# Logic-Analyzer-01.net
KiCad netlist of a schematic drawn in Altium Designer
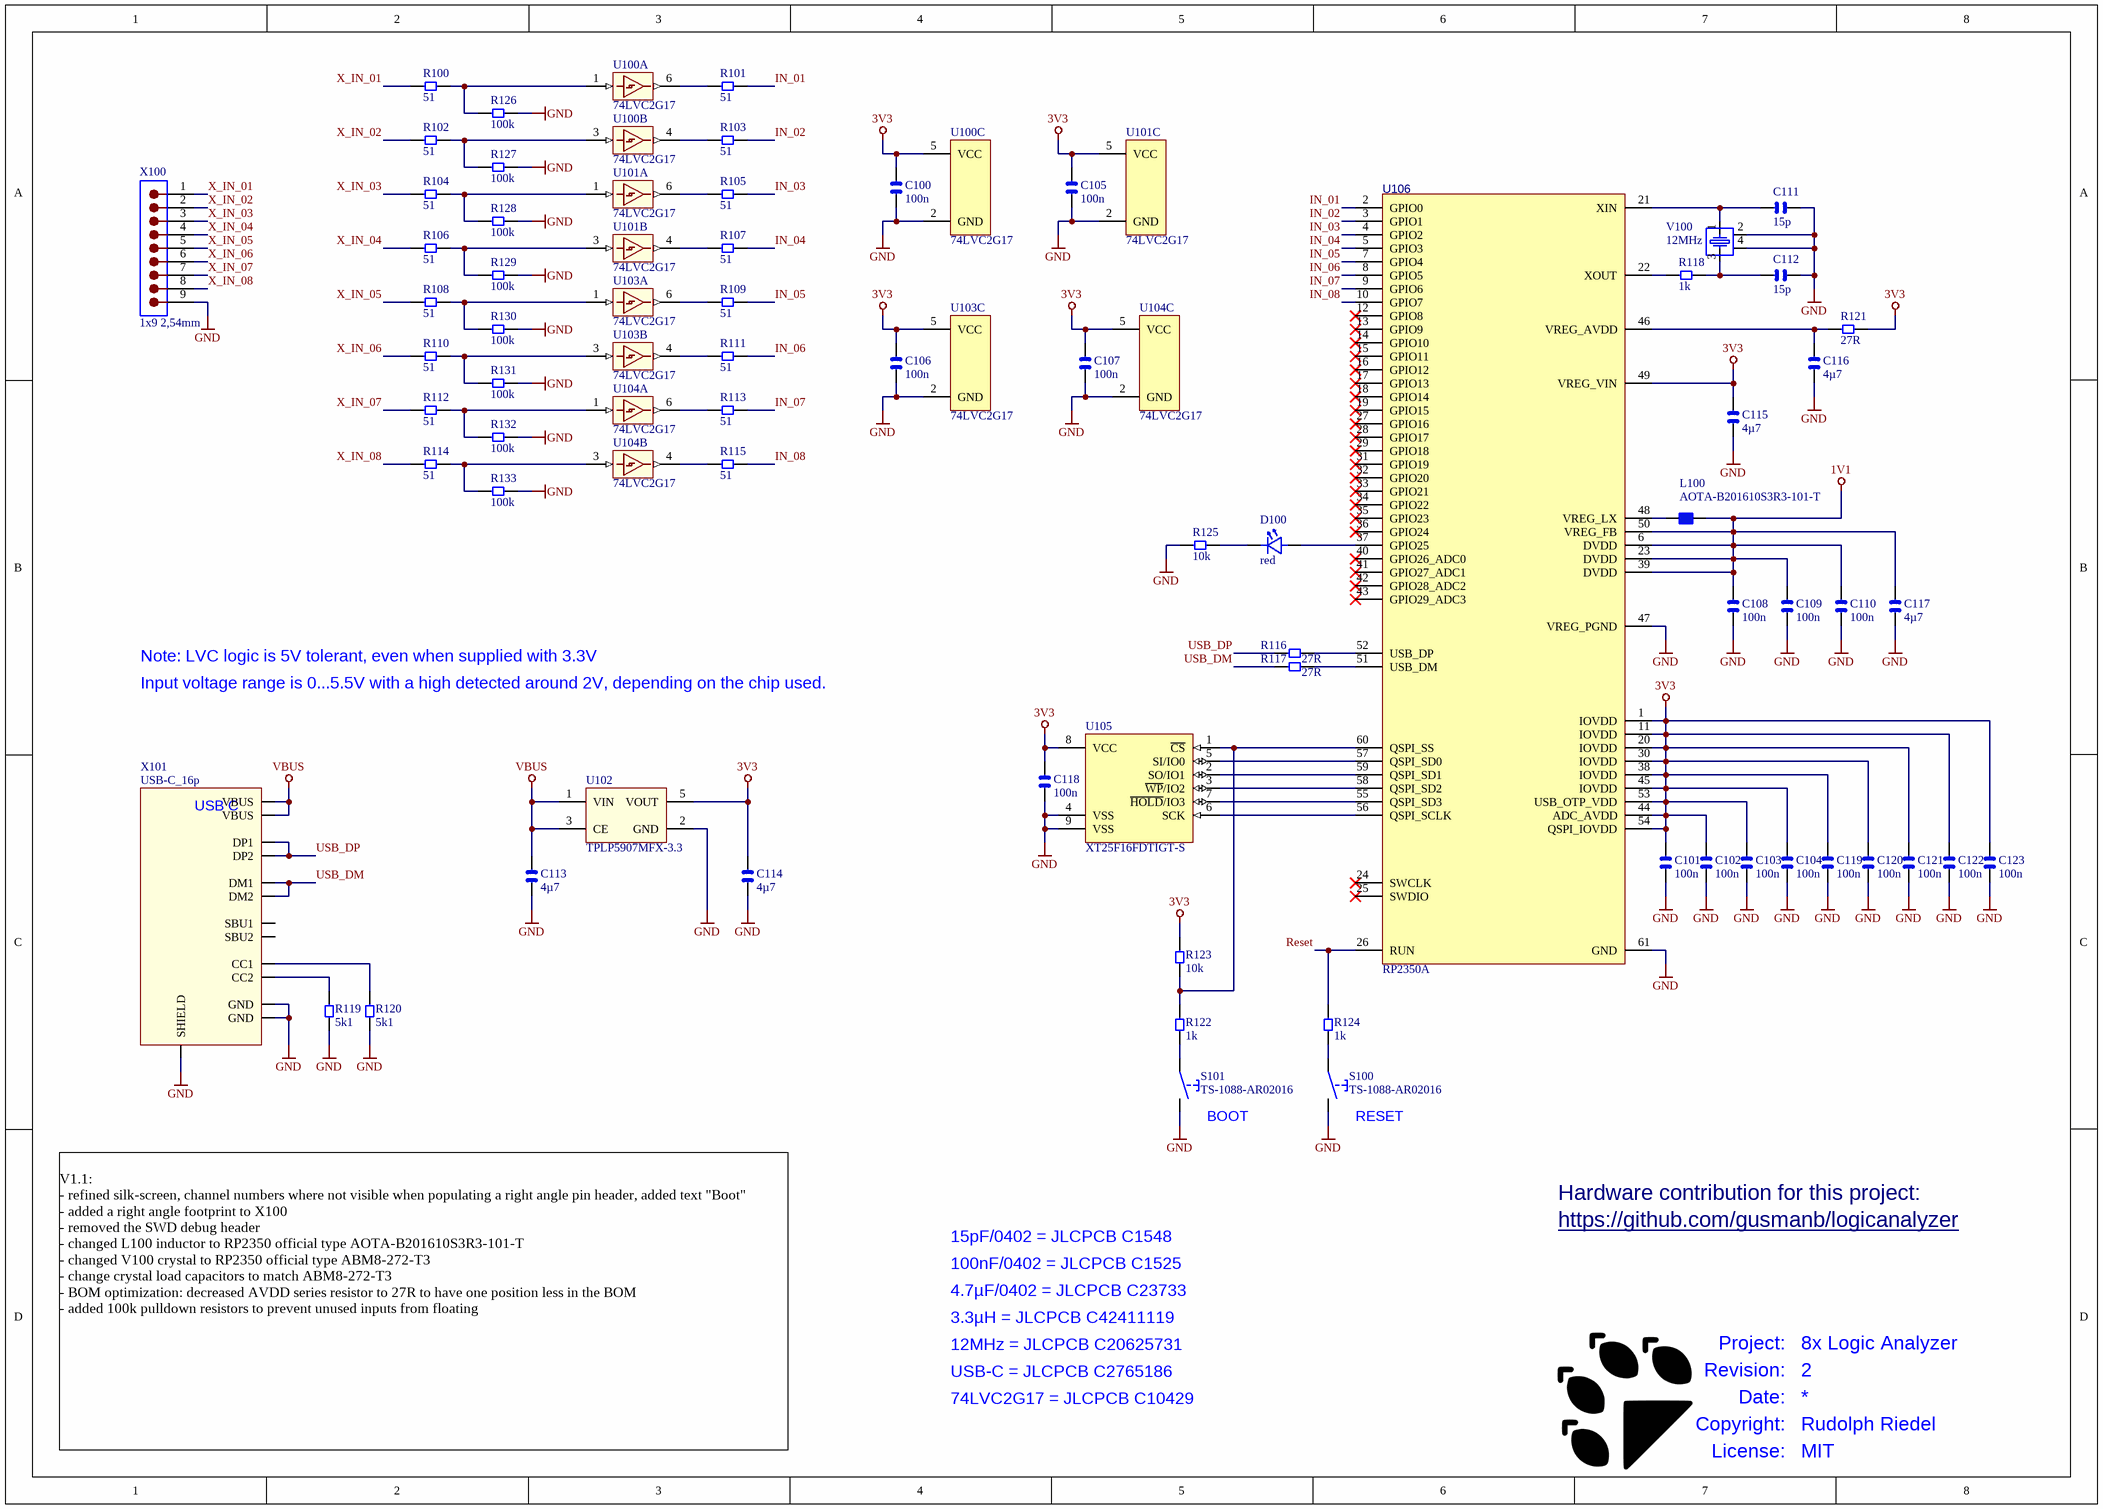
[diagram p0: Logic-Analyzer-01.SchDoc]

(export (version "E")
  (design (tool "Eeschema 10.0.6"))
  (components
    (comp (ref "C100")
      (value "100n")
      (footprint "CAPC1005X06N")
      (description "0402 Chip Capacitor")
      (fields (field (name "PART NUMBER") "CAPC_0402") (field (name "EDITOR") "rriedel"))
      (libsource (lib "HW-Labor_GF") (part "CAP_2_V2"))
    )
    (comp (ref "C101")
      (value "100n")
      (footprint "CAPC1005X06N")
      (description "0402 Chip Capacitor")
      (fields (field (name "PART NUMBER") "CAPC_0402") (field (name "EDITOR") "rriedel"))
      (libsource (lib "HW-Labor_GF") (part "CAP_2_V2"))
    )
    (comp (ref "C102")
      (value "100n")
      (footprint "CAPC1005X06N")
      (description "0402 Chip Capacitor")
      (fields (field (name "PART NUMBER") "CAPC_0402") (field (name "EDITOR") "rriedel"))
      (libsource (lib "HW-Labor_GF") (part "CAP_2_V2"))
    )
    (comp (ref "C103")
      (value "100n")
      (footprint "CAPC1005X06N")
      (description "0402 Chip Capacitor")
      (fields (field (name "PART NUMBER") "CAPC_0402") (field (name "EDITOR") "rriedel"))
      (libsource (lib "HW-Labor_GF") (part "CAP_2_V2"))
    )
    (comp (ref "C104")
      (value "100n")
      (footprint "CAPC1005X06N")
      (description "0402 Chip Capacitor")
      (fields (field (name "PART NUMBER") "CAPC_0402") (field (name "EDITOR") "rriedel"))
      (libsource (lib "HW-Labor_GF") (part "CAP_2_V2"))
    )
    (comp (ref "C105")
      (value "100n")
      (footprint "CAPC1005X06N")
      (description "0402 Chip Capacitor")
      (fields (field (name "PART NUMBER") "CAPC_0402") (field (name "EDITOR") "rriedel"))
      (libsource (lib "HW-Labor_GF") (part "CAP_2_V2"))
    )
    (comp (ref "C106")
      (value "100n")
      (footprint "CAPC1005X06N")
      (description "0402 Chip Capacitor")
      (fields (field (name "PART NUMBER") "CAPC_0402") (field (name "EDITOR") "rriedel"))
      (libsource (lib "HW-Labor_GF") (part "CAP_2_V2"))
    )
    (comp (ref "C107")
      (value "100n")
      (footprint "CAPC1005X06N")
      (description "0402 Chip Capacitor")
      (fields (field (name "PART NUMBER") "CAPC_0402") (field (name "EDITOR") "rriedel"))
      (libsource (lib "HW-Labor_GF") (part "CAP_2_V2"))
    )
    (comp (ref "C108")
      (value "100n")
      (footprint "CAPC1005X06N")
      (description "0402 Chip Capacitor")
      (fields (field (name "PART NUMBER") "CAPC_0402") (field (name "EDITOR") "rriedel"))
      (libsource (lib "HW-Labor_GF") (part "CAP_2_V2"))
    )
    (comp (ref "C109")
      (value "100n")
      (footprint "CAPC1005X06N")
      (description "0402 Chip Capacitor")
      (fields (field (name "PART NUMBER") "CAPC_0402") (field (name "EDITOR") "rriedel"))
      (libsource (lib "HW-Labor_GF") (part "CAP_2_V2"))
    )
    (comp (ref "C110")
      (value "100n")
      (footprint "CAPC1005X06N")
      (description "0402 Chip Capacitor")
      (fields (field (name "PART NUMBER") "CAPC_0402") (field (name "EDITOR") "rriedel"))
      (libsource (lib "HW-Labor_GF") (part "CAP_2_V2"))
    )
    (comp (ref "C111")
      (value "15p")
      (footprint "CAPC1005X06N")
      (description "0402 Chip Capacitor")
      (fields (field (name "PART NUMBER") "CAPC_0402") (field (name "EDITOR") "rriedel"))
      (libsource (lib "HW-Labor_GF") (part "CAP_2_V2"))
    )
    (comp (ref "C112")
      (value "15p")
      (footprint "CAPC1005X06N")
      (description "0402 Chip Capacitor")
      (fields (field (name "PART NUMBER") "CAPC_0402") (field (name "EDITOR") "rriedel"))
      (libsource (lib "HW-Labor_GF") (part "CAP_2_V2"))
    )
    (comp (ref "C113")
      (value "4µ7")
      (footprint "CAPC1005X06N")
      (description "0402 Chip Capacitor")
      (fields (field (name "PART NUMBER") "CAPC_0402") (field (name "EDITOR") "rriedel"))
      (libsource (lib "HW-Labor_GF") (part "CAP_2_V2"))
    )
    (comp (ref "C114")
      (value "4µ7")
      (footprint "CAPC1005X06N")
      (description "0402 Chip Capacitor")
      (fields (field (name "PART NUMBER") "CAPC_0402") (field (name "EDITOR") "rriedel"))
      (libsource (lib "HW-Labor_GF") (part "CAP_2_V2"))
    )
    (comp (ref "C115")
      (value "4µ7")
      (footprint "CAPC1005X06N")
      (description "0402 Chip Capacitor")
      (fields (field (name "PART NUMBER") "CAPC_0402") (field (name "EDITOR") "rriedel"))
      (libsource (lib "HW-Labor_GF") (part "CAP_2_V2"))
    )
    (comp (ref "C116")
      (value "4µ7")
      (footprint "CAPC1005X06N")
      (description "0402 Chip Capacitor")
      (fields (field (name "PART NUMBER") "CAPC_0402") (field (name "EDITOR") "rriedel"))
      (libsource (lib "HW-Labor_GF") (part "CAP_2_V2"))
    )
    (comp (ref "C117")
      (value "4µ7")
      (footprint "CAPC1005X06N")
      (description "0402 Chip Capacitor")
      (fields (field (name "PART NUMBER") "CAPC_0402") (field (name "EDITOR") "rriedel"))
      (libsource (lib "HW-Labor_GF") (part "CAP_2_V2"))
    )
    (comp (ref "C118")
      (value "100n")
      (footprint "CAPC1005X06N")
      (description "0402 Chip Capacitor")
      (fields (field (name "PART NUMBER") "CAPC_0402") (field (name "EDITOR") "rriedel"))
      (libsource (lib "HW-Labor_GF") (part "CAP_2_V2"))
    )
    (comp (ref "C119")
      (value "100n")
      (footprint "CAPC1005X06N")
      (description "0402 Chip Capacitor")
      (fields (field (name "PART NUMBER") "CAPC_0402") (field (name "EDITOR") "rriedel"))
      (libsource (lib "HW-Labor_GF") (part "CAP_2_V2"))
    )
    (comp (ref "C120")
      (value "100n")
      (footprint "CAPC1005X06N")
      (description "0402 Chip Capacitor")
      (fields (field (name "PART NUMBER") "CAPC_0402") (field (name "EDITOR") "rriedel"))
      (libsource (lib "HW-Labor_GF") (part "CAP_2_V2"))
    )
    (comp (ref "C121")
      (value "100n")
      (footprint "CAPC1005X06N")
      (description "0402 Chip Capacitor")
      (fields (field (name "PART NUMBER") "CAPC_0402") (field (name "EDITOR") "rriedel"))
      (libsource (lib "HW-Labor_GF") (part "CAP_2_V2"))
    )
    (comp (ref "C122")
      (value "100n")
      (footprint "CAPC1005X06N")
      (description "0402 Chip Capacitor")
      (fields (field (name "PART NUMBER") "CAPC_0402") (field (name "EDITOR") "rriedel"))
      (libsource (lib "HW-Labor_GF") (part "CAP_2_V2"))
    )
    (comp (ref "C123")
      (value "100n")
      (footprint "CAPC1005X06N")
      (description "0402 Chip Capacitor")
      (fields (field (name "PART NUMBER") "CAPC_0402") (field (name "EDITOR") "rriedel"))
      (libsource (lib "HW-Labor_GF") (part "CAP_2_V2"))
    )
    (comp (ref "D100")
      (value "red")
      (footprint "DIOC1608X06N_LED")
      (description "LED, 0603")
      (fields (field (name "PART NUMBER") "LED_0603") (field (name "EDITOR") "rriedel"))
      (libsource (lib "HW-Labor_GF") (part "LED_generic"))
    )
    (comp (ref "L100")
      (value "AOTA-B201610S3R3-101-T")
      (footprint "PowerInductor_2.0x1.6")
      (description "3.3µH, 2.8A, 2.0mm x 1.6mm x 1.0mm")
      (fields
        (field (name "MANUFACTURER") "Abracom")
        (field (name "DISTRIBUTOR_1_PART_NUMBER") "C42411119")
        (field (name "EDITOR") "rriedel")
      )
      (libsource (lib "HW-Labor_GF") (part "IND_2_V1"))
    )
    (comp (ref "R100")
      (value "51")
      (footprint "RESC1608X06L")
      (description "0603 Chip Resistor")
      (fields (field (name "PART NUMBER") "RESC_0603") (field (name "EDITOR") "rriedel"))
      (libsource (lib "HW-Labor_GF") (part "RES_2_V2"))
    )
    (comp (ref "R101")
      (value "51")
      (footprint "RESC1608X06L")
      (description "0603 Chip Resistor")
      (fields (field (name "PART NUMBER") "RESC_0603") (field (name "EDITOR") "rriedel"))
      (libsource (lib "HW-Labor_GF") (part "RES_2_V2"))
    )
    (comp (ref "R102")
      (value "51")
      (footprint "RESC1608X06L")
      (description "0603 Chip Resistor")
      (fields (field (name "PART NUMBER") "RESC_0603") (field (name "EDITOR") "rriedel"))
      (libsource (lib "HW-Labor_GF") (part "RES_2_V2"))
    )
    (comp (ref "R103")
      (value "51")
      (footprint "RESC1608X06L")
      (description "0603 Chip Resistor")
      (fields (field (name "PART NUMBER") "RESC_0603") (field (name "EDITOR") "rriedel"))
      (libsource (lib "HW-Labor_GF") (part "RES_2_V2"))
    )
    (comp (ref "R104")
      (value "51")
      (footprint "RESC1608X06L")
      (description "0603 Chip Resistor")
      (fields (field (name "PART NUMBER") "RESC_0603") (field (name "EDITOR") "rriedel"))
      (libsource (lib "HW-Labor_GF") (part "RES_2_V2"))
    )
    (comp (ref "R105")
      (value "51")
      (footprint "RESC1608X06L")
      (description "0603 Chip Resistor")
      (fields (field (name "PART NUMBER") "RESC_0603") (field (name "EDITOR") "rriedel"))
      (libsource (lib "HW-Labor_GF") (part "RES_2_V2"))
    )
    (comp (ref "R106")
      (value "51")
      (footprint "RESC1608X06L")
      (description "0603 Chip Resistor")
      (fields (field (name "PART NUMBER") "RESC_0603") (field (name "EDITOR") "rriedel"))
      (libsource (lib "HW-Labor_GF") (part "RES_2_V2"))
    )
    (comp (ref "R107")
      (value "51")
      (footprint "RESC1608X06L")
      (description "0603 Chip Resistor")
      (fields (field (name "PART NUMBER") "RESC_0603") (field (name "EDITOR") "rriedel"))
      (libsource (lib "HW-Labor_GF") (part "RES_2_V2"))
    )
    (comp (ref "R108")
      (value "51")
      (footprint "RESC1608X06L")
      (description "0603 Chip Resistor")
      (fields (field (name "PART NUMBER") "RESC_0603") (field (name "EDITOR") "rriedel"))
      (libsource (lib "HW-Labor_GF") (part "RES_2_V2"))
    )
    (comp (ref "R109")
      (value "51")
      (footprint "RESC1608X06L")
      (description "0603 Chip Resistor")
      (fields (field (name "PART NUMBER") "RESC_0603") (field (name "EDITOR") "rriedel"))
      (libsource (lib "HW-Labor_GF") (part "RES_2_V2"))
    )
    (comp (ref "R110")
      (value "51")
      (footprint "RESC1608X06L")
      (description "0603 Chip Resistor")
      (fields (field (name "PART NUMBER") "RESC_0603") (field (name "EDITOR") "rriedel"))
      (libsource (lib "HW-Labor_GF") (part "RES_2_V2"))
    )
    (comp (ref "R111")
      (value "51")
      (footprint "RESC1608X06L")
      (description "0603 Chip Resistor")
      (fields (field (name "PART NUMBER") "RESC_0603") (field (name "EDITOR") "rriedel"))
      (libsource (lib "HW-Labor_GF") (part "RES_2_V2"))
    )
    (comp (ref "R112")
      (value "51")
      (footprint "RESC1608X06L")
      (description "0603 Chip Resistor")
      (fields (field (name "PART NUMBER") "RESC_0603") (field (name "EDITOR") "rriedel"))
      (libsource (lib "HW-Labor_GF") (part "RES_2_V2"))
    )
    (comp (ref "R113")
      (value "51")
      (footprint "RESC1608X06L")
      (description "0603 Chip Resistor")
      (fields (field (name "PART NUMBER") "RESC_0603") (field (name "EDITOR") "rriedel"))
      (libsource (lib "HW-Labor_GF") (part "RES_2_V2"))
    )
    (comp (ref "R114")
      (value "51")
      (footprint "RESC1608X06L")
      (description "0603 Chip Resistor")
      (fields (field (name "PART NUMBER") "RESC_0603") (field (name "EDITOR") "rriedel"))
      (libsource (lib "HW-Labor_GF") (part "RES_2_V2"))
    )
    (comp (ref "R115")
      (value "51")
      (footprint "RESC1608X06L")
      (description "0603 Chip Resistor")
      (fields (field (name "PART NUMBER") "RESC_0603") (field (name "EDITOR") "rriedel"))
      (libsource (lib "HW-Labor_GF") (part "RES_2_V2"))
    )
    (comp (ref "R116")
      (value "27R")
      (footprint "RESC1608X06L")
      (description "0603 Chip Resistor")
      (fields (field (name "PART NUMBER") "RESC_0603") (field (name "EDITOR") "rriedel"))
      (libsource (lib "HW-Labor_GF") (part "RES_2_V2"))
    )
    (comp (ref "R117")
      (value "27R")
      (footprint "RESC1608X06L")
      (description "0603 Chip Resistor")
      (fields (field (name "PART NUMBER") "RESC_0603") (field (name "EDITOR") "rriedel"))
      (libsource (lib "HW-Labor_GF") (part "RES_2_V2"))
    )
    (comp (ref "R118")
      (value "1k")
      (footprint "RESC1608X06L")
      (description "0603 Chip Resistor")
      (fields (field (name "PART NUMBER") "RESC_0603") (field (name "EDITOR") "rriedel"))
      (libsource (lib "HW-Labor_GF") (part "RES_2_V2"))
    )
    (comp (ref "R119")
      (value "5k1")
      (footprint "RESC1608X06L")
      (description "0603 Chip Resistor")
      (fields (field (name "PART NUMBER") "RESC_0603") (field (name "EDITOR") "rriedel"))
      (libsource (lib "HW-Labor_GF") (part "RES_2_V2"))
    )
    (comp (ref "R120")
      (value "5k1")
      (footprint "RESC1608X06L")
      (description "0603 Chip Resistor")
      (fields (field (name "PART NUMBER") "RESC_0603") (field (name "EDITOR") "rriedel"))
      (libsource (lib "HW-Labor_GF") (part "RES_2_V2"))
    )
    (comp (ref "R121")
      (value "27R")
      (footprint "RESC1608X06L")
      (description "0603 Chip Resistor")
      (fields (field (name "PART NUMBER") "RESC_0603") (field (name "EDITOR") "rriedel"))
      (libsource (lib "HW-Labor_GF") (part "RES_2_V2"))
    )
    (comp (ref "R122")
      (value "1k")
      (footprint "RESC1608X06L")
      (description "0603 Chip Resistor")
      (fields (field (name "PART NUMBER") "RESC_0603") (field (name "EDITOR") "rriedel"))
      (libsource (lib "HW-Labor_GF") (part "RES_2_V2"))
    )
    (comp (ref "R123")
      (value "10k")
      (footprint "RESC1608X06L")
      (description "0603 Chip Resistor")
      (fields (field (name "PART NUMBER") "RESC_0603") (field (name "EDITOR") "rriedel"))
      (libsource (lib "HW-Labor_GF") (part "RES_2_V2"))
    )
    (comp (ref "R124")
      (value "1k")
      (footprint "RESC1608X06L")
      (description "0603 Chip Resistor")
      (fields (field (name "PART NUMBER") "RESC_0603") (field (name "EDITOR") "rriedel"))
      (libsource (lib "HW-Labor_GF") (part "RES_2_V2"))
    )
    (comp (ref "R125")
      (value "10k")
      (footprint "RESC1608X06L")
      (description "0603 Chip Resistor")
      (fields (field (name "PART NUMBER") "RESC_0603") (field (name "EDITOR") "rriedel"))
      (libsource (lib "HW-Labor_GF") (part "RES_2_V2"))
    )
    (comp (ref "R126")
      (value "100k")
      (footprint "RESC1005X06N")
      (description "0402 Chip Resistor")
      (fields (field (name "PART NUMBER") "RESC_0402") (field (name "EDITOR") "rriedel"))
      (libsource (lib "HW-Labor_GF") (part "RES_2_V2"))
    )
    (comp (ref "R127")
      (value "100k")
      (footprint "RESC1005X06N")
      (description "0402 Chip Resistor")
      (fields (field (name "PART NUMBER") "RESC_0402") (field (name "EDITOR") "rriedel"))
      (libsource (lib "HW-Labor_GF") (part "RES_2_V2"))
    )
    (comp (ref "R128")
      (value "100k")
      (footprint "RESC1005X06N")
      (description "0402 Chip Resistor")
      (fields (field (name "PART NUMBER") "RESC_0402") (field (name "EDITOR") "rriedel"))
      (libsource (lib "HW-Labor_GF") (part "RES_2_V2"))
    )
    (comp (ref "R129")
      (value "100k")
      (footprint "RESC1005X06N")
      (description "0402 Chip Resistor")
      (fields (field (name "PART NUMBER") "RESC_0402") (field (name "EDITOR") "rriedel"))
      (libsource (lib "HW-Labor_GF") (part "RES_2_V2"))
    )
    (comp (ref "R130")
      (value "100k")
      (footprint "RESC1005X06N")
      (description "0402 Chip Resistor")
      (fields (field (name "PART NUMBER") "RESC_0402") (field (name "EDITOR") "rriedel"))
      (libsource (lib "HW-Labor_GF") (part "RES_2_V2"))
    )
    (comp (ref "R131")
      (value "100k")
      (footprint "RESC1005X06N")
      (description "0402 Chip Resistor")
      (fields (field (name "PART NUMBER") "RESC_0402") (field (name "EDITOR") "rriedel"))
      (libsource (lib "HW-Labor_GF") (part "RES_2_V2"))
    )
    (comp (ref "R132")
      (value "100k")
      (footprint "RESC1005X06N")
      (description "0402 Chip Resistor")
      (fields (field (name "PART NUMBER") "RESC_0402") (field (name "EDITOR") "rriedel"))
      (libsource (lib "HW-Labor_GF") (part "RES_2_V2"))
    )
    (comp (ref "R133")
      (value "100k")
      (footprint "RESC1005X06N")
      (description "0402 Chip Resistor")
      (fields (field (name "PART NUMBER") "RESC_0402") (field (name "EDITOR") "rriedel"))
      (libsource (lib "HW-Labor_GF") (part "RES_2_V2"))
    )
    (comp (ref "S100")
      (value "TS-1088-AR02016")
      (footprint "TS-1088-AR02016")
      (description "Tact Switch, 4x3x2, 2pin, 12V/50mA")
      (fields
        (field (name "MANUFACTURER") "XunPu")
        (field (name "DISTRIBUTOR_1_PART_NUMBER") "C720477")
        (field (name "EDITOR") "rriedel")
      )
      (libsource (lib "HW-Labor_GF") (part "Tact_Switch"))
    )
    (comp (ref "S101")
      (value "TS-1088-AR02016")
      (footprint "TS-1088-AR02016")
      (description "Tact Switch, 4x3x2, 2pin, 12V/50mA")
      (fields
        (field (name "MANUFACTURER") "XunPu")
        (field (name "DISTRIBUTOR_1_PART_NUMBER") "C720477")
        (field (name "EDITOR") "rriedel")
      )
      (libsource (lib "HW-Labor_GF") (part "Tact_Switch"))
    )
    (comp (ref "U100")
      (value "74LVC2G17")
      (footprint "SOT95P280X110-6N")
      (description "Dual Schmitt-Trigger Buffer with 5.5V tolerant inputs")
      (fields
        (field (name "MANUFACTURER") "TI")
        (field (name "DISTRIBUTOR_1_PART_NUMBER") "296-SN74LVC2G17DBVRCT-ND‎")
        (field (name "EDITOR") "rriedel")
      )
      (libsource (lib "HW-Labor_GF") (part "74LVC2G17"))
    )
    (comp (ref "U101")
      (value "74LVC2G17")
      (footprint "SOT95P280X110-6N")
      (description "Dual Schmitt-Trigger Buffer with 5.5V tolerant inputs")
      (fields
        (field (name "MANUFACTURER") "TI")
        (field (name "DISTRIBUTOR_1_PART_NUMBER") "296-SN74LVC2G17DBVRCT-ND‎")
        (field (name "EDITOR") "rriedel")
      )
      (libsource (lib "HW-Labor_GF") (part "74LVC2G17"))
    )
    (comp (ref "U102")
      (value "TPLP5907MFX-3.3")
      (footprint "SOT95P280X110-5N")
      (description "100 mA LDO,  Vout= 3,3V, -40°C..125°C")
      (fields
        (field (name "PART NUMBER") "MIC5233-3.3")
        (field (name "MANUFACTURER") "Microchip")
        (field (name "EDITOR") "rriedel")
      )
      (libsource (lib "HW-Labor_GF") (part "LDO_SOT23-5"))
    )
    (comp (ref "U103")
      (value "74LVC2G17")
      (footprint "SOT95P280X110-6N")
      (description "Dual Schmitt-Trigger Buffer with 5.5V tolerant inputs")
      (fields
        (field (name "MANUFACTURER") "TI")
        (field (name "DISTRIBUTOR_1_PART_NUMBER") "296-SN74LVC2G17DBVRCT-ND‎")
        (field (name "EDITOR") "rriedel")
      )
      (libsource (lib "HW-Labor_GF") (part "74LVC2G17"))
    )
    (comp (ref "U104")
      (value "74LVC2G17")
      (footprint "SOT95P280X110-6N")
      (description "Dual Schmitt-Trigger Buffer with 5.5V tolerant inputs")
      (fields
        (field (name "MANUFACTURER") "TI")
        (field (name "DISTRIBUTOR_1_PART_NUMBER") "296-SN74LVC2G17DBVRCT-ND‎")
        (field (name "EDITOR") "rriedel")
      )
      (libsource (lib "HW-Labor_GF") (part "74LVC2G17"))
    )
    (comp (ref "U105")
      (value "XT25F16FDTIGT-S")
      (footprint "USONP50X200X300X8N")
      (description "SPI NOR FLASH, 16MBit")
      (fields
        (field (name "MANUFACTURER") "XTX")
        (field (name "DISTRIBUTOR_1_PART_NUMBER") "C29781641")
        (field (name "EDITOR") "rriedel")
      )
      (libsource (lib "HW-Labor_GF") (part "SPI_NOR_USON8"))
    )
    (comp (ref "U106")
      (value "RP2350A")
      (footprint "QFN40P700X700X085-60EP")
      (description "32-bit Microcontroller, 2x 150MHz Cortex M33")
      (fields (field (name "MANUFACTURER") "Raspberry") (field (name "EDITOR") "rriedel"))
      (libsource (lib "HW-Labor_GF") (part "RP2350A"))
    )
    (comp (ref "V100")
      (value "12MHz")
      (footprint "ABM8")
      (description "-40℃~+85℃, 12MHz, Cl=10pF, ±30ppm, SMD3225-4P")
      (fields
        (field (name "PART NUMBER") "ABM8-272-T3")
        (field (name "MANUFACTURER") "Abracom")
        (field (name "EDITOR") "rriedel")
      )
      (libsource (lib "HW-Labor_GF") (part "XTAL_SMD-4"))
    )
    (comp (ref "X100")
      (value "1x9 2,54mm")
      (footprint "PINH_1x09_2_54mm_RA")
      (description "Pin-Header 2,54 mm 9pins")
      (fields (field (name "PART NUMBER") "PINH_1x9_2_54") (field (name "EDITOR") "rriedel"))
      (libsource (lib "HW-Labor_GF") (part "CONM_1x9_V2"))
    )
    (comp (ref "X101")
      (value "USB-C_16p")
      (footprint "USBC_16P")
      (description "SMD USB-C 16p")
      (fields (field (name "DISTRIBUTOR_1_PART_NUMBER") "C2765186") (field (name "EDITOR") "rriedel"))
      (libsource (lib "HW-Labor_GF") (part "USB-C"))
    )
  )
  (nets
    (net (code "1") (name "/IN_01") (class "Default")
      (node (ref "R101") (pin "2") (pinfunction "2_2") (pintype "passive"))
      (node (ref "U106") (pin "2") (pinfunction "GPIO0_2") (pintype "passive"))
    )
    (net (code "2") (name "/IN_02") (class "Default")
      (node (ref "R103") (pin "2") (pinfunction "2_2") (pintype "passive"))
      (node (ref "U106") (pin "3") (pinfunction "GPIO1_3") (pintype "passive"))
    )
    (net (code "3") (name "/IN_03") (class "Default")
      (node (ref "R105") (pin "2") (pinfunction "2_2") (pintype "passive"))
      (node (ref "U106") (pin "4") (pinfunction "GPIO2_4") (pintype "passive"))
    )
    (net (code "4") (name "/IN_04") (class "Default")
      (node (ref "R107") (pin "2") (pinfunction "2_2") (pintype "passive"))
      (node (ref "U106") (pin "5") (pinfunction "GPIO3_5") (pintype "passive"))
    )
    (net (code "5") (name "/IN_05") (class "Default")
      (node (ref "R109") (pin "2") (pinfunction "2_2") (pintype "passive"))
      (node (ref "U106") (pin "7") (pinfunction "GPIO4_7") (pintype "passive"))
    )
    (net (code "6") (name "/IN_06") (class "Default")
      (node (ref "R111") (pin "2") (pinfunction "2_2") (pintype "passive"))
      (node (ref "U106") (pin "8") (pinfunction "GPIO5_8") (pintype "passive"))
    )
    (net (code "7") (name "/IN_07") (class "Default")
      (node (ref "R113") (pin "2") (pinfunction "2_2") (pintype "passive"))
      (node (ref "U106") (pin "9") (pinfunction "GPIO6_9") (pintype "passive"))
    )
    (net (code "8") (name "/IN_08") (class "Default")
      (node (ref "R115") (pin "2") (pinfunction "2_2") (pintype "passive"))
      (node (ref "U106") (pin "10") (pinfunction "GPIO7_10") (pintype "passive"))
    )
    (net (code "9") (name "/Reset") (class "Default")
      (node (ref "R124") (pin "2") (pinfunction "2_2") (pintype "passive"))
      (node (ref "U106") (pin "26") (pinfunction "RUN_26") (pintype "passive"))
    )
    (net (code "10") (name "/USB_DM") (class "Default")
      (node (ref "R117") (pin "1") (pinfunction "1_1") (pintype "passive"))
      (node (ref "X101") (pin "A7") (pinfunction "DM1_A7") (pintype "passive"))
      (node (ref "X101") (pin "B7") (pinfunction "DM2_B7") (pintype "passive"))
    )
    (net (code "11") (name "/USB_DP") (class "Default")
      (node (ref "R116") (pin "1") (pinfunction "1_1") (pintype "passive"))
      (node (ref "X101") (pin "A6") (pinfunction "DP1_A6") (pintype "passive"))
      (node (ref "X101") (pin "B6") (pinfunction "DP2_B6") (pintype "passive"))
    )
    (net (code "12") (name "/X_IN_01") (class "Default")
      (node (ref "R100") (pin "1") (pinfunction "1_1") (pintype "passive"))
      (node (ref "X100") (pin "1") (pinfunction "1_1") (pintype "passive"))
    )
    (net (code "13") (name "/X_IN_02") (class "Default")
      (node (ref "R102") (pin "1") (pinfunction "1_1") (pintype "passive"))
      (node (ref "X100") (pin "2") (pinfunction "2_2") (pintype "passive"))
    )
    (net (code "14") (name "/X_IN_03") (class "Default")
      (node (ref "R104") (pin "1") (pinfunction "1_1") (pintype "passive"))
      (node (ref "X100") (pin "3") (pinfunction "3_3") (pintype "passive"))
    )
    (net (code "15") (name "/X_IN_04") (class "Default")
      (node (ref "R106") (pin "1") (pinfunction "1_1") (pintype "passive"))
      (node (ref "X100") (pin "4") (pinfunction "4_4") (pintype "passive"))
    )
    (net (code "16") (name "/X_IN_05") (class "Default")
      (node (ref "R108") (pin "1") (pinfunction "1_1") (pintype "passive"))
      (node (ref "X100") (pin "5") (pinfunction "5_5") (pintype "passive"))
    )
    (net (code "17") (name "/X_IN_06") (class "Default")
      (node (ref "R110") (pin "1") (pinfunction "1_1") (pintype "passive"))
      (node (ref "X100") (pin "6") (pinfunction "6_6") (pintype "passive"))
    )
    (net (code "18") (name "/X_IN_07") (class "Default")
      (node (ref "R112") (pin "1") (pinfunction "1_1") (pintype "passive"))
      (node (ref "X100") (pin "7") (pinfunction "7_7") (pintype "passive"))
    )
    (net (code "19") (name "/X_IN_08") (class "Default")
      (node (ref "R114") (pin "1") (pinfunction "1_1") (pintype "passive"))
      (node (ref "X100") (pin "8") (pinfunction "8_8") (pintype "passive"))
    )
    (net (code "20") (name "1V1") (class "Default")
      (node (ref "C108") (pin "2") (pinfunction "2_2") (pintype "passive"))
      (node (ref "C109") (pin "2") (pinfunction "2_2") (pintype "passive"))
      (node (ref "C110") (pin "2") (pinfunction "2_2") (pintype "passive"))
      (node (ref "C117") (pin "2") (pinfunction "2_2") (pintype "passive"))
      (node (ref "L100") (pin "1") (pinfunction "1_1") (pintype "passive"))
      (node (ref "U106") (pin "23") (pinfunction "DVDD_23") (pintype "power_in"))
      (node (ref "U106") (pin "39") (pinfunction "DVDD_39") (pintype "power_in"))
      (node (ref "U106") (pin "50") (pinfunction "VREG_FB_50") (pintype "passive"))
      (node (ref "U106") (pin "6") (pinfunction "DVDD_6") (pintype "power_in"))
    )
    (net (code "21") (name "3V3") (class "Default")
      (node (ref "C100") (pin "2") (pinfunction "2_2") (pintype "passive"))
      (node (ref "C101") (pin "2") (pinfunction "2_2") (pintype "passive"))
      (node (ref "C102") (pin "2") (pinfunction "2_2") (pintype "passive"))
      (node (ref "C103") (pin "2") (pinfunction "2_2") (pintype "passive"))
      (node (ref "C104") (pin "2") (pinfunction "2_2") (pintype "passive"))
      (node (ref "C105") (pin "2") (pinfunction "2_2") (pintype "passive"))
      (node (ref "C106") (pin "2") (pinfunction "2_2") (pintype "passive"))
      (node (ref "C107") (pin "2") (pinfunction "2_2") (pintype "passive"))
      (node (ref "C114") (pin "2") (pinfunction "2_2") (pintype "passive"))
      (node (ref "C115") (pin "2") (pinfunction "2_2") (pintype "passive"))
      (node (ref "C118") (pin "2") (pinfunction "2_2") (pintype "passive"))
      (node (ref "C119") (pin "2") (pinfunction "2_2") (pintype "passive"))
      (node (ref "C120") (pin "2") (pinfunction "2_2") (pintype "passive"))
      (node (ref "C121") (pin "2") (pinfunction "2_2") (pintype "passive"))
      (node (ref "C122") (pin "2") (pinfunction "2_2") (pintype "passive"))
      (node (ref "C123") (pin "2") (pinfunction "2_2") (pintype "passive"))
      (node (ref "R121") (pin "2") (pinfunction "2_2") (pintype "passive"))
      (node (ref "R123") (pin "2") (pinfunction "2_2") (pintype "passive"))
      (node (ref "U100") (pin "5") (pinfunction "VCC_5") (pintype "power_in"))
      (node (ref "U101") (pin "5") (pinfunction "VCC_5") (pintype "power_in"))
      (node (ref "U102") (pin "5") (pinfunction "VOUT_5") (pintype "passive"))
      (node (ref "U103") (pin "5") (pinfunction "VCC_5") (pintype "power_in"))
      (node (ref "U104") (pin "5") (pinfunction "VCC_5") (pintype "power_in"))
      (node (ref "U105") (pin "8") (pinfunction "VCC_8") (pintype "power_in"))
      (node (ref "U106") (pin "1") (pinfunction "IOVDD_1") (pintype "power_in"))
      (node (ref "U106") (pin "11") (pinfunction "IOVDD_11") (pintype "power_in"))
      (node (ref "U106") (pin "20") (pinfunction "IOVDD_20") (pintype "power_in"))
      (node (ref "U106") (pin "30") (pinfunction "IOVDD_30") (pintype "power_in"))
      (node (ref "U106") (pin "38") (pinfunction "IOVDD_38") (pintype "power_in"))
      (node (ref "U106") (pin "44") (pinfunction "ADC_AVDD_44") (pintype "power_in"))
      (node (ref "U106") (pin "45") (pinfunction "IOVDD_45") (pintype "power_in"))
      (node (ref "U106") (pin "49") (pinfunction "VREG_VIN_49") (pintype "power_in"))
      (node (ref "U106") (pin "53") (pinfunction "USB_OTP_VDD_53") (pintype "power_in"))
      (node (ref "U106") (pin "54") (pinfunction "QSPI_IOVDD_54") (pintype "power_in"))
    )
    (net (code "22") (name "GND") (class "Default")
      (node (ref "C100") (pin "1") (pinfunction "1_1") (pintype "passive"))
      (node (ref "C101") (pin "1") (pinfunction "1_1") (pintype "passive"))
      (node (ref "C102") (pin "1") (pinfunction "1_1") (pintype "passive"))
      (node (ref "C103") (pin "1") (pinfunction "1_1") (pintype "passive"))
      (node (ref "C104") (pin "1") (pinfunction "1_1") (pintype "passive"))
      (node (ref "C105") (pin "1") (pinfunction "1_1") (pintype "passive"))
      (node (ref "C106") (pin "1") (pinfunction "1_1") (pintype "passive"))
      (node (ref "C107") (pin "1") (pinfunction "1_1") (pintype "passive"))
      (node (ref "C108") (pin "1") (pinfunction "1_1") (pintype "passive"))
      (node (ref "C109") (pin "1") (pinfunction "1_1") (pintype "passive"))
      (node (ref "C110") (pin "1") (pinfunction "1_1") (pintype "passive"))
      (node (ref "C111") (pin "1") (pinfunction "1_1") (pintype "passive"))
      (node (ref "C112") (pin "1") (pinfunction "1_1") (pintype "passive"))
      (node (ref "C113") (pin "1") (pinfunction "1_1") (pintype "passive"))
      (node (ref "C114") (pin "1") (pinfunction "1_1") (pintype "passive"))
      (node (ref "C115") (pin "1") (pinfunction "1_1") (pintype "passive"))
      (node (ref "C116") (pin "1") (pinfunction "1_1") (pintype "passive"))
      (node (ref "C117") (pin "1") (pinfunction "1_1") (pintype "passive"))
      (node (ref "C118") (pin "1") (pinfunction "1_1") (pintype "passive"))
      (node (ref "C119") (pin "1") (pinfunction "1_1") (pintype "passive"))
      (node (ref "C120") (pin "1") (pinfunction "1_1") (pintype "passive"))
      (node (ref "C121") (pin "1") (pinfunction "1_1") (pintype "passive"))
      (node (ref "C122") (pin "1") (pinfunction "1_1") (pintype "passive"))
      (node (ref "C123") (pin "1") (pinfunction "1_1") (pintype "passive"))
      (node (ref "R119") (pin "1") (pinfunction "1_1") (pintype "passive"))
      (node (ref "R120") (pin "1") (pinfunction "1_1") (pintype "passive"))
      (node (ref "R125") (pin "2") (pinfunction "2_2") (pintype "passive"))
      (node (ref "R126") (pin "2") (pinfunction "2_2") (pintype "passive"))
      (node (ref "R127") (pin "2") (pinfunction "2_2") (pintype "passive"))
      (node (ref "R128") (pin "2") (pinfunction "2_2") (pintype "passive"))
      (node (ref "R129") (pin "2") (pinfunction "2_2") (pintype "passive"))
      (node (ref "R130") (pin "2") (pinfunction "2_2") (pintype "passive"))
      (node (ref "R131") (pin "2") (pinfunction "2_2") (pintype "passive"))
      (node (ref "R132") (pin "2") (pinfunction "2_2") (pintype "passive"))
      (node (ref "R133") (pin "2") (pinfunction "2_2") (pintype "passive"))
      (node (ref "S100") (pin "2") (pinfunction "2_2") (pintype "passive"))
      (node (ref "S101") (pin "2") (pinfunction "2_2") (pintype "passive"))
      (node (ref "U100") (pin "2") (pinfunction "GND_2") (pintype "power_in"))
      (node (ref "U101") (pin "2") (pinfunction "GND_2") (pintype "power_in"))
      (node (ref "U102") (pin "2") (pinfunction "GND_2") (pintype "passive"))
      (node (ref "U103") (pin "2") (pinfunction "GND_2") (pintype "power_in"))
      (node (ref "U104") (pin "2") (pinfunction "GND_2") (pintype "power_in"))
      (node (ref "U105") (pin "4") (pinfunction "VSS_4") (pintype "power_in"))
      (node (ref "U105") (pin "9") (pinfunction "VSS_9") (pintype "power_in"))
      (node (ref "U106") (pin "47") (pinfunction "VREG_PGND_47") (pintype "passive"))
      (node (ref "U106") (pin "61") (pinfunction "GND_61") (pintype "power_in"))
      (node (ref "V100") (pin "2") (pintype "passive"))
      (node (ref "V100") (pin "4") (pintype "passive"))
      (node (ref "X100") (pin "9") (pinfunction "9_9") (pintype "passive"))
      (node (ref "X101") (pin "A1-B12") (pinfunction "GND_A1-B12") (pintype "power_in"))
      (node (ref "X101") (pin "B1-A12") (pinfunction "GND_B1-A12") (pintype "power_in"))
      (node (ref "X101") (pin "SHIELD") (pinfunction "SHIELD_SHIELD") (pintype "passive"))
    )
    (net (code "23") (name "Net-(C112-Pad2)") (class "Default")
      (node (ref "C112") (pin "2") (pinfunction "2_2") (pintype "passive"))
      (node (ref "R118") (pin "2") (pinfunction "2_2") (pintype "passive"))
      (node (ref "V100") (pin "3") (pintype "passive"))
    )
    (net (code "24") (name "Net-(D100-Pad1)") (class "Default")
      (node (ref "D100") (pin "1") (pinfunction "1_1") (pintype "passive"))
      (node (ref "R125") (pin "1") (pinfunction "1_1") (pintype "passive"))
    )
    (net (code "25") (name "Net-(R122-Pad1)") (class "Default")
      (node (ref "R122") (pin "1") (pinfunction "1_1") (pintype "passive"))
      (node (ref "S101") (pin "1") (pinfunction "1_1") (pintype "passive"))
    )
    (net (code "26") (name "Net-(R124-Pad1)") (class "Default")
      (node (ref "R124") (pin "1") (pinfunction "1_1") (pintype "passive"))
      (node (ref "S100") (pin "1") (pinfunction "1_1") (pintype "passive"))
    )
    (net (code "27") (name "Net-(U100A-1A)") (class "Default")
      (node (ref "R100") (pin "2") (pinfunction "2_2") (pintype "passive"))
      (node (ref "R126") (pin "1") (pinfunction "1_1") (pintype "passive"))
      (node (ref "U100") (pin "1") (pinfunction "1A_1") (pintype "input"))
    )
    (net (code "28") (name "Net-(U100A-1Y)") (class "Default")
      (node (ref "R101") (pin "1") (pinfunction "1_1") (pintype "passive"))
      (node (ref "U100") (pin "6") (pinfunction "1Y_6") (pintype "output"))
    )
    (net (code "29") (name "Net-(U100B-2A)") (class "Default")
      (node (ref "R102") (pin "2") (pinfunction "2_2") (pintype "passive"))
      (node (ref "R127") (pin "1") (pinfunction "1_1") (pintype "passive"))
      (node (ref "U100") (pin "3") (pinfunction "2A_3") (pintype "input"))
    )
    (net (code "30") (name "Net-(U100B-2Y)") (class "Default")
      (node (ref "R103") (pin "1") (pinfunction "1_1") (pintype "passive"))
      (node (ref "U100") (pin "4") (pinfunction "2Y_4") (pintype "output"))
    )
    (net (code "31") (name "Net-(U101A-1A)") (class "Default")
      (node (ref "R104") (pin "2") (pinfunction "2_2") (pintype "passive"))
      (node (ref "R128") (pin "1") (pinfunction "1_1") (pintype "passive"))
      (node (ref "U101") (pin "1") (pinfunction "1A_1") (pintype "input"))
    )
    (net (code "32") (name "Net-(U101A-1Y)") (class "Default")
      (node (ref "R105") (pin "1") (pinfunction "1_1") (pintype "passive"))
      (node (ref "U101") (pin "6") (pinfunction "1Y_6") (pintype "output"))
    )
    (net (code "33") (name "Net-(U101B-2A)") (class "Default")
      (node (ref "R106") (pin "2") (pinfunction "2_2") (pintype "passive"))
      (node (ref "R129") (pin "1") (pinfunction "1_1") (pintype "passive"))
      (node (ref "U101") (pin "3") (pinfunction "2A_3") (pintype "input"))
    )
    (net (code "34") (name "Net-(U101B-2Y)") (class "Default")
      (node (ref "R107") (pin "1") (pinfunction "1_1") (pintype "passive"))
      (node (ref "U101") (pin "4") (pinfunction "2Y_4") (pintype "output"))
    )
    (net (code "35") (name "Net-(U103A-1A)") (class "Default")
      (node (ref "R108") (pin "2") (pinfunction "2_2") (pintype "passive"))
      (node (ref "R130") (pin "1") (pinfunction "1_1") (pintype "passive"))
      (node (ref "U103") (pin "1") (pinfunction "1A_1") (pintype "input"))
    )
    (net (code "36") (name "Net-(U103A-1Y)") (class "Default")
      (node (ref "R109") (pin "1") (pinfunction "1_1") (pintype "passive"))
      (node (ref "U103") (pin "6") (pinfunction "1Y_6") (pintype "output"))
    )
    (net (code "37") (name "Net-(U103B-2A)") (class "Default")
      (node (ref "R110") (pin "2") (pinfunction "2_2") (pintype "passive"))
      (node (ref "R131") (pin "1") (pinfunction "1_1") (pintype "passive"))
      (node (ref "U103") (pin "3") (pinfunction "2A_3") (pintype "input"))
    )
    (net (code "38") (name "Net-(U103B-2Y)") (class "Default")
      (node (ref "R111") (pin "1") (pinfunction "1_1") (pintype "passive"))
      (node (ref "U103") (pin "4") (pinfunction "2Y_4") (pintype "output"))
    )
    (net (code "39") (name "Net-(U104A-1A)") (class "Default")
      (node (ref "R112") (pin "2") (pinfunction "2_2") (pintype "passive"))
      (node (ref "R132") (pin "1") (pinfunction "1_1") (pintype "passive"))
      (node (ref "U104") (pin "1") (pinfunction "1A_1") (pintype "input"))
    )
    (net (code "40") (name "Net-(U104A-1Y)") (class "Default")
      (node (ref "R113") (pin "1") (pinfunction "1_1") (pintype "passive"))
      (node (ref "U104") (pin "6") (pinfunction "1Y_6") (pintype "output"))
    )
    (net (code "41") (name "Net-(U104B-2A)") (class "Default")
      (node (ref "R114") (pin "2") (pinfunction "2_2") (pintype "passive"))
      (node (ref "R133") (pin "1") (pinfunction "1_1") (pintype "passive"))
      (node (ref "U104") (pin "3") (pinfunction "2A_3") (pintype "input"))
    )
    (net (code "42") (name "Net-(U104B-2Y)") (class "Default")
      (node (ref "R115") (pin "1") (pinfunction "1_1") (pintype "passive"))
      (node (ref "U104") (pin "4") (pinfunction "2Y_4") (pintype "output"))
    )
    (net (code "43") (name "Net-(U105-SCK)") (class "Default")
      (node (ref "U105") (pin "6") (pinfunction "SCK_6") (pintype "input"))
      (node (ref "U106") (pin "56") (pinfunction "QSPI_SCLK_56") (pintype "passive"))
    )
    (net (code "44") (name "Net-(U105-SI{slash}IO0)") (class "Default")
      (node (ref "U105") (pin "5") (pinfunction "SI/IO0_5") (pintype "bidirectional"))
      (node (ref "U106") (pin "57") (pinfunction "QSPI_SD0_57") (pintype "passive"))
    )
    (net (code "45") (name "Net-(U105-SO{slash}IO1)") (class "Default")
      (node (ref "U105") (pin "2") (pinfunction "SO/IO1_2") (pintype "bidirectional"))
      (node (ref "U106") (pin "59") (pinfunction "QSPI_SD1_59") (pintype "passive"))
    )
    (net (code "46") (name "Net-(U105-~{CS})") (class "Default")
      (node (ref "R122") (pin "2") (pinfunction "2_2") (pintype "passive"))
      (node (ref "R123") (pin "1") (pinfunction "1_1") (pintype "passive"))
      (node (ref "U105") (pin "1") (pinfunction "~{CS}_1") (pintype "input"))
      (node (ref "U106") (pin "60") (pinfunction "QSPI_SS_60") (pintype "passive"))
    )
    (net (code "47") (name "Net-(U105-~{HOLD}{slash}IO3)") (class "Default")
      (node (ref "U105") (pin "7") (pinfunction "~{HOLD}/IO3_7") (pintype "bidirectional"))
      (node (ref "U106") (pin "55") (pinfunction "QSPI_SD3_55") (pintype "passive"))
    )
    (net (code "48") (name "Net-(U105-~{WP}{slash}IO2)") (class "Default")
      (node (ref "U105") (pin "3") (pinfunction "~{WP}/IO2_3") (pintype "bidirectional"))
      (node (ref "U106") (pin "58") (pinfunction "QSPI_SD2_58") (pintype "passive"))
    )
    (net (code "49") (name "Net-(U106-GPIO25)") (class "Default")
      (node (ref "D100") (pin "2") (pinfunction "2_2") (pintype "passive"))
      (node (ref "U106") (pin "37") (pinfunction "GPIO25_37") (pintype "passive"))
    )
    (net (code "50") (name "Net-(U106-USB_DM)") (class "Default")
      (node (ref "R117") (pin "2") (pinfunction "2_2") (pintype "passive"))
      (node (ref "U106") (pin "51") (pinfunction "USB_DM_51") (pintype "passive"))
    )
    (net (code "51") (name "Net-(U106-USB_DP)") (class "Default")
      (node (ref "R116") (pin "2") (pinfunction "2_2") (pintype "passive"))
      (node (ref "U106") (pin "52") (pinfunction "USB_DP_52") (pintype "passive"))
    )
    (net (code "52") (name "Net-(U106-VREG_AVDD)") (class "Default")
      (node (ref "C116") (pin "2") (pinfunction "2_2") (pintype "passive"))
      (node (ref "R121") (pin "1") (pinfunction "1_1") (pintype "passive"))
      (node (ref "U106") (pin "46") (pinfunction "VREG_AVDD_46") (pintype "power_in"))
    )
    (net (code "53") (name "Net-(U106-VREG_LX)") (class "Default")
      (node (ref "L100") (pin "2") (pinfunction "2_2") (pintype "passive"))
      (node (ref "U106") (pin "48") (pinfunction "VREG_LX_48") (pintype "passive"))
    )
    (net (code "54") (name "Net-(U106-XIN)") (class "Default")
      (node (ref "C111") (pin "2") (pinfunction "2_2") (pintype "passive"))
      (node (ref "U106") (pin "21") (pinfunction "XIN_21") (pintype "passive"))
      (node (ref "V100") (pin "1") (pintype "passive"))
    )
    (net (code "55") (name "Net-(U106-XOUT)") (class "Default")
      (node (ref "R118") (pin "1") (pinfunction "1_1") (pintype "passive"))
      (node (ref "U106") (pin "22") (pinfunction "XOUT_22") (pintype "passive"))
    )
    (net (code "56") (name "Net-(X101-CC1)") (class "Default")
      (node (ref "R120") (pin "2") (pinfunction "2_2") (pintype "passive"))
      (node (ref "X101") (pin "A5") (pinfunction "CC1_A5") (pintype "passive"))
    )
    (net (code "57") (name "Net-(X101-CC2)") (class "Default")
      (node (ref "R119") (pin "2") (pinfunction "2_2") (pintype "passive"))
      (node (ref "X101") (pin "B5") (pinfunction "CC2_B5") (pintype "passive"))
    )
    (net (code "58") (name "VBUS") (class "Default")
      (node (ref "C113") (pin "2") (pinfunction "2_2") (pintype "passive"))
      (node (ref "U102") (pin "1") (pinfunction "VIN_1") (pintype "passive"))
      (node (ref "U102") (pin "3") (pinfunction "CE_3") (pintype "passive"))
      (node (ref "X101") (pin "A4-B9") (pinfunction "VBUS_A4-B9") (pintype "power_in"))
      (node (ref "X101") (pin "B4-A9") (pinfunction "VBUS_B4-A9") (pintype "power_in"))
    )
    (net (code "59") (name "unconnected-(U106-GPIO8-Pad12)") (class "Default")
      (node (ref "U106") (pin "12") (pinfunction "GPIO8_12") (pintype "passive+no_connect"))
    )
    (net (code "60") (name "unconnected-(U106-GPIO9-Pad13)") (class "Default")
      (node (ref "U106") (pin "13") (pinfunction "GPIO9_13") (pintype "passive+no_connect"))
    )
    (net (code "61") (name "unconnected-(U106-GPIO10-Pad14)") (class "Default")
      (node (ref "U106") (pin "14") (pinfunction "GPIO10_14") (pintype "passive+no_connect"))
    )
    (net (code "62") (name "unconnected-(U106-GPIO11-Pad15)") (class "Default")
      (node (ref "U106") (pin "15") (pinfunction "GPIO11_15") (pintype "passive+no_connect"))
    )
    (net (code "63") (name "unconnected-(U106-GPIO12-Pad16)") (class "Default")
      (node (ref "U106") (pin "16") (pinfunction "GPIO12_16") (pintype "passive+no_connect"))
    )
    (net (code "64") (name "unconnected-(U106-GPIO13-Pad17)") (class "Default")
      (node (ref "U106") (pin "17") (pinfunction "GPIO13_17") (pintype "passive+no_connect"))
    )
    (net (code "65") (name "unconnected-(U106-GPIO14-Pad18)") (class "Default")
      (node (ref "U106") (pin "18") (pinfunction "GPIO14_18") (pintype "passive+no_connect"))
    )
    (net (code "66") (name "unconnected-(U106-GPIO15-Pad19)") (class "Default")
      (node (ref "U106") (pin "19") (pinfunction "GPIO15_19") (pintype "passive+no_connect"))
    )
    (net (code "67") (name "unconnected-(U106-GPIO16-Pad27)") (class "Default")
      (node (ref "U106") (pin "27") (pinfunction "GPIO16_27") (pintype "passive+no_connect"))
    )
    (net (code "68") (name "unconnected-(U106-GPIO17-Pad28)") (class "Default")
      (node (ref "U106") (pin "28") (pinfunction "GPIO17_28") (pintype "passive+no_connect"))
    )
    (net (code "69") (name "unconnected-(U106-GPIO18-Pad29)") (class "Default")
      (node (ref "U106") (pin "29") (pinfunction "GPIO18_29") (pintype "passive+no_connect"))
    )
    (net (code "70") (name "unconnected-(U106-GPIO19-Pad31)") (class "Default")
      (node (ref "U106") (pin "31") (pinfunction "GPIO19_31") (pintype "passive+no_connect"))
    )
    (net (code "71") (name "unconnected-(U106-GPIO20-Pad32)") (class "Default")
      (node (ref "U106") (pin "32") (pinfunction "GPIO20_32") (pintype "passive+no_connect"))
    )
    (net (code "72") (name "unconnected-(U106-GPIO21-Pad33)") (class "Default")
      (node (ref "U106") (pin "33") (pinfunction "GPIO21_33") (pintype "passive+no_connect"))
    )
    (net (code "73") (name "unconnected-(U106-GPIO22-Pad34)") (class "Default")
      (node (ref "U106") (pin "34") (pinfunction "GPIO22_34") (pintype "passive+no_connect"))
    )
    (net (code "74") (name "unconnected-(U106-GPIO23-Pad35)") (class "Default")
      (node (ref "U106") (pin "35") (pinfunction "GPIO23_35") (pintype "passive+no_connect"))
    )
    (net (code "75") (name "unconnected-(U106-GPIO24-Pad36)") (class "Default")
      (node (ref "U106") (pin "36") (pinfunction "GPIO24_36") (pintype "passive+no_connect"))
    )
    (net (code "76") (name "unconnected-(U106-GPIO26_ADC0-Pad40)") (class "Default")
      (node (ref "U106") (pin "40") (pinfunction "GPIO26_ADC0_40") (pintype "passive+no_connect"))
    )
    (net (code "77") (name "unconnected-(U106-GPIO27_ADC1-Pad41)") (class "Default")
      (node (ref "U106") (pin "41") (pinfunction "GPIO27_ADC1_41") (pintype "passive+no_connect"))
    )
    (net (code "78") (name "unconnected-(U106-GPIO28_ADC2-Pad42)") (class "Default")
      (node (ref "U106") (pin "42") (pinfunction "GPIO28_ADC2_42") (pintype "passive+no_connect"))
    )
    (net (code "79") (name "unconnected-(U106-GPIO29_ADC3-Pad43)") (class "Default")
      (node (ref "U106") (pin "43") (pinfunction "GPIO29_ADC3_43") (pintype "passive+no_connect"))
    )
    (net (code "80") (name "unconnected-(U106-SWCLK-Pad24)") (class "Default")
      (node (ref "U106") (pin "24") (pinfunction "SWCLK_24") (pintype "passive+no_connect"))
    )
    (net (code "81") (name "unconnected-(U106-SWDIO-Pad25)") (class "Default")
      (node (ref "U106") (pin "25") (pinfunction "SWDIO_25") (pintype "passive+no_connect"))
    )
    (net (code "82") (name "unconnected-(X101-SBU1-PadA8)") (class "Default")
      (node (ref "X101") (pin "A8") (pinfunction "SBU1_A8") (pintype "passive"))
    )
    (net (code "83") (name "unconnected-(X101-SBU2-PadB8)") (class "Default")
      (node (ref "X101") (pin "B8") (pinfunction "SBU2_B8") (pintype "passive"))
    )
  )
)
